# OscillatorShield.net
KiCad netlist of a schematic drawn in EAGLE
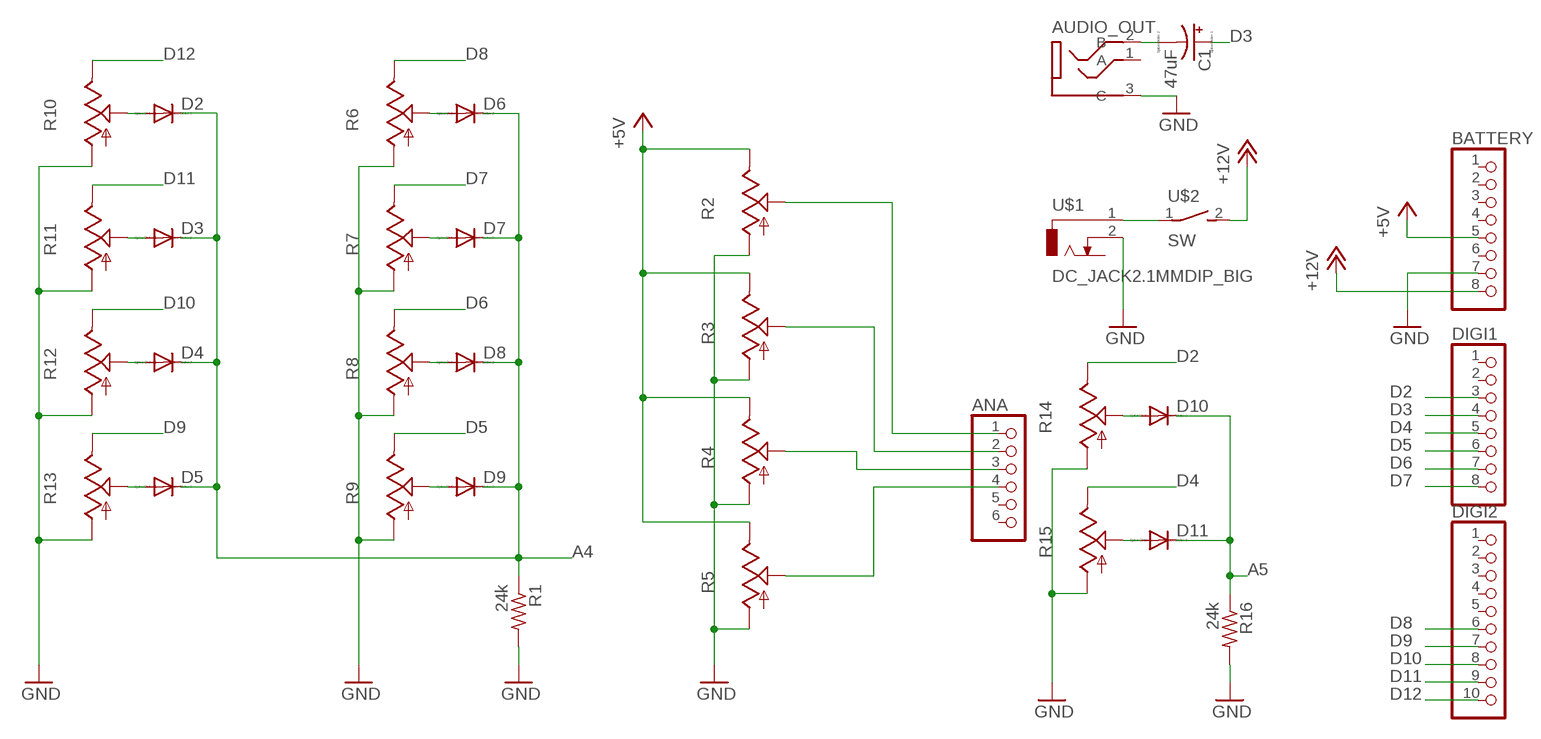
[diagram p0: schematic, sheet 1]

(export (version "E")
  (design (tool "Eeschema 10.0.6"))
  (components
    (comp (ref "ANA")
      (value "PINHD-1X6")
      (footprint "eagle-import:1X06")
      (libsource (lib "eagle-import") (part "PINHD-1X6"))
    )
    (comp (ref "AUDIO_OUT")
      (value "3CON_3.5MMPLUG")
      (footprint "eagle-import:3PIN_DIP")
      (libsource (lib "eagle-import") (part "3CON_3.5MMPLUG"))
    )
    (comp (ref "BATTERY")
      (value "PINHD-1X8")
      (footprint "eagle-import:1X08")
      (libsource (lib "eagle-import") (part "PINHD-1X8"))
    )
    (comp (ref "C1")
      (value "47uF")
      (footprint "eagle-import:E2,5-6")
      (libsource (lib "eagle-import") (part "CPOL-USE2.5-6"))
    )
    (comp (ref "D2")
      (value "DIODE-SOD123")
      (footprint "eagle-import:SOD123")
      (libsource (lib "eagle-import") (part "DIODE-SOD123"))
    )
    (comp (ref "D3")
      (value "DIODE-SOD123")
      (footprint "eagle-import:SOD123")
      (libsource (lib "eagle-import") (part "DIODE-SOD123"))
    )
    (comp (ref "D4")
      (value "DIODE-SOD123")
      (footprint "eagle-import:SOD123")
      (libsource (lib "eagle-import") (part "DIODE-SOD123"))
    )
    (comp (ref "D5")
      (value "DIODE-SOD123")
      (footprint "eagle-import:SOD123")
      (libsource (lib "eagle-import") (part "DIODE-SOD123"))
    )
    (comp (ref "D6")
      (value "DIODE-SOD123")
      (footprint "eagle-import:SOD123")
      (libsource (lib "eagle-import") (part "DIODE-SOD123"))
    )
    (comp (ref "D7")
      (value "DIODE-SOD123")
      (footprint "eagle-import:SOD123")
      (libsource (lib "eagle-import") (part "DIODE-SOD123"))
    )
    (comp (ref "D8")
      (value "DIODE-SOD123")
      (footprint "eagle-import:SOD123")
      (libsource (lib "eagle-import") (part "DIODE-SOD123"))
    )
    (comp (ref "D9")
      (value "DIODE-SOD123")
      (footprint "eagle-import:SOD123")
      (libsource (lib "eagle-import") (part "DIODE-SOD123"))
    )
    (comp (ref "D10")
      (value "DIODE-SOD123")
      (footprint "eagle-import:SOD123")
      (libsource (lib "eagle-import") (part "DIODE-SOD123"))
    )
    (comp (ref "D11")
      (value "DIODE-SOD123")
      (footprint "eagle-import:SOD123")
      (libsource (lib "eagle-import") (part "DIODE-SOD123"))
    )
    (comp (ref "DIGI1")
      (value "PINHD-1X8")
      (footprint "eagle-import:1X08")
      (libsource (lib "eagle-import") (part "PINHD-1X8"))
    )
    (comp (ref "DIGI2")
      (value "PINHD-1X10")
      (footprint "eagle-import:1X10")
      (libsource (lib "eagle-import") (part "PINHD-1X10"))
    )
    (comp (ref "R1")
      (value "24k")
      (footprint "eagle-import:R1206")
      (libsource (lib "eagle-import") (part "R-US_R1206"))
    )
    (comp (ref "R2")
      (value "TRIM_US-RJ9W")
      (footprint "eagle-import:RJ9W")
      (libsource (lib "eagle-import") (part "TRIM_US-RJ9W"))
    )
    (comp (ref "R3")
      (value "TRIM_US-RJ9W")
      (footprint "eagle-import:RJ9W")
      (libsource (lib "eagle-import") (part "TRIM_US-RJ9W"))
    )
    (comp (ref "R4")
      (value "TRIM_US-RJ9W")
      (footprint "eagle-import:RJ9W")
      (libsource (lib "eagle-import") (part "TRIM_US-RJ9W"))
    )
    (comp (ref "R5")
      (value "TRIM_US-RJ9W")
      (footprint "eagle-import:RJ9W")
      (libsource (lib "eagle-import") (part "TRIM_US-RJ9W"))
    )
    (comp (ref "R6")
      (value "TRIM_US-RJ9W")
      (footprint "eagle-import:RJ9W")
      (libsource (lib "eagle-import") (part "TRIM_US-RJ9W"))
    )
    (comp (ref "R7")
      (value "TRIM_US-RJ9W")
      (footprint "eagle-import:RJ9W")
      (libsource (lib "eagle-import") (part "TRIM_US-RJ9W"))
    )
    (comp (ref "R8")
      (value "TRIM_US-RJ9W")
      (footprint "eagle-import:RJ9W")
      (libsource (lib "eagle-import") (part "TRIM_US-RJ9W"))
    )
    (comp (ref "R9")
      (value "TRIM_US-RJ9W")
      (footprint "eagle-import:RJ9W")
      (libsource (lib "eagle-import") (part "TRIM_US-RJ9W"))
    )
    (comp (ref "R10")
      (value "TRIM_US-RJ9W")
      (footprint "eagle-import:RJ9W")
      (libsource (lib "eagle-import") (part "TRIM_US-RJ9W"))
    )
    (comp (ref "R11")
      (value "TRIM_US-RJ9W")
      (footprint "eagle-import:RJ9W")
      (libsource (lib "eagle-import") (part "TRIM_US-RJ9W"))
    )
    (comp (ref "R12")
      (value "TRIM_US-RJ9W")
      (footprint "eagle-import:RJ9W")
      (libsource (lib "eagle-import") (part "TRIM_US-RJ9W"))
    )
    (comp (ref "R13")
      (value "TRIM_US-RJ9W")
      (footprint "eagle-import:RJ9W")
      (libsource (lib "eagle-import") (part "TRIM_US-RJ9W"))
    )
    (comp (ref "R14")
      (value "TRIM_US-RJ9W")
      (footprint "eagle-import:RJ9W")
      (libsource (lib "eagle-import") (part "TRIM_US-RJ9W"))
    )
    (comp (ref "R15")
      (value "TRIM_US-RJ9W")
      (footprint "eagle-import:RJ9W")
      (libsource (lib "eagle-import") (part "TRIM_US-RJ9W"))
    )
    (comp (ref "R16")
      (value "24k")
      (footprint "eagle-import:R1206")
      (libsource (lib "eagle-import") (part "R-US_R1206"))
    )
    (comp (ref "U$1")
      (value "DC_JACK2.1MMDIP_BIG")
      (footprint "eagle-import:2PIN_DIP_BIG")
      (libsource (lib "eagle-import") (part "DC_JACK2.1MMDIP_BIG"))
    )
    (comp (ref "U$2")
      (value "SW")
      (footprint "eagle-import:2PIN_DIP_BIG")
      (libsource (lib "eagle-import") (part "SW"))
    )
  )
  (nets
    (net (code "1") (name "+5V") (class "Default")
      (node (ref "BATTERY") (pin "5") (pinfunction "5_5") (pintype "passive"))
      (node (ref "R2") (pin "E") (pinfunction "E_E") (pintype "passive"))
      (node (ref "R3") (pin "E") (pinfunction "E_E") (pintype "passive"))
      (node (ref "R4") (pin "E") (pinfunction "E_E") (pintype "passive"))
      (node (ref "R5") (pin "E") (pinfunction "E_E") (pintype "passive"))
    )
    (net (code "2") (name "+12V") (class "Default")
      (node (ref "BATTERY") (pin "8") (pinfunction "8_8") (pintype "passive"))
      (node (ref "U$2") (pin "2") (pinfunction "S_2") (pintype "passive"))
    )
    (net (code "3") (name "/A4") (class "Default")
      (node (ref "D2") (pin "C") (pinfunction "C_C") (pintype "passive"))
      (node (ref "D3") (pin "C") (pinfunction "C_C") (pintype "passive"))
      (node (ref "D4") (pin "C") (pinfunction "C_C") (pintype "passive"))
      (node (ref "D5") (pin "C") (pinfunction "C_C") (pintype "passive"))
      (node (ref "D6") (pin "C") (pinfunction "C_C") (pintype "passive"))
      (node (ref "D7") (pin "C") (pinfunction "C_C") (pintype "passive"))
      (node (ref "D8") (pin "C") (pinfunction "C_C") (pintype "passive"))
      (node (ref "D9") (pin "C") (pinfunction "C_C") (pintype "passive"))
      (node (ref "R1") (pin "1") (pinfunction "1_1") (pintype "passive"))
    )
    (net (code "4") (name "/A5") (class "Default")
      (node (ref "D10") (pin "C") (pinfunction "C_C") (pintype "passive"))
      (node (ref "D11") (pin "C") (pinfunction "C_C") (pintype "passive"))
      (node (ref "R16") (pin "1") (pinfunction "1_1") (pintype "passive"))
    )
    (net (code "5") (name "/D2") (class "Default")
      (node (ref "DIGI1") (pin "3") (pinfunction "3_3") (pintype "passive"))
      (node (ref "R14") (pin "E") (pinfunction "E_E") (pintype "passive"))
    )
    (net (code "6") (name "/D3") (class "Default")
      (node (ref "C1") (pin "+") (pinfunction "+_+") (pintype "passive"))
      (node (ref "DIGI1") (pin "4") (pinfunction "4_4") (pintype "passive"))
    )
    (net (code "7") (name "/D4") (class "Default")
      (node (ref "DIGI1") (pin "5") (pinfunction "5_5") (pintype "passive"))
      (node (ref "R15") (pin "E") (pinfunction "E_E") (pintype "passive"))
    )
    (net (code "8") (name "/D5") (class "Default")
      (node (ref "DIGI1") (pin "6") (pinfunction "6_6") (pintype "passive"))
      (node (ref "R9") (pin "E") (pinfunction "E_E") (pintype "passive"))
    )
    (net (code "9") (name "/D6") (class "Default")
      (node (ref "DIGI1") (pin "7") (pinfunction "7_7") (pintype "passive"))
      (node (ref "R8") (pin "E") (pinfunction "E_E") (pintype "passive"))
    )
    (net (code "10") (name "/D7") (class "Default")
      (node (ref "DIGI1") (pin "8") (pinfunction "8_8") (pintype "passive"))
      (node (ref "R7") (pin "E") (pinfunction "E_E") (pintype "passive"))
    )
    (net (code "11") (name "/D8") (class "Default")
      (node (ref "DIGI2") (pin "6") (pinfunction "6_6") (pintype "passive"))
      (node (ref "R6") (pin "E") (pinfunction "E_E") (pintype "passive"))
    )
    (net (code "12") (name "/D9") (class "Default")
      (node (ref "DIGI2") (pin "7") (pinfunction "7_7") (pintype "passive"))
      (node (ref "R13") (pin "E") (pinfunction "E_E") (pintype "passive"))
    )
    (net (code "13") (name "/D10") (class "Default")
      (node (ref "DIGI2") (pin "8") (pinfunction "8_8") (pintype "passive"))
      (node (ref "R12") (pin "E") (pinfunction "E_E") (pintype "passive"))
    )
    (net (code "14") (name "/D11") (class "Default")
      (node (ref "DIGI2") (pin "9") (pinfunction "9_9") (pintype "passive"))
      (node (ref "R11") (pin "E") (pinfunction "E_E") (pintype "passive"))
    )
    (net (code "15") (name "/D12") (class "Default")
      (node (ref "DIGI2") (pin "10") (pinfunction "10_10") (pintype "passive"))
      (node (ref "R10") (pin "E") (pinfunction "E_E") (pintype "passive"))
    )
    (net (code "16") (name "GND") (class "Default")
      (node (ref "AUDIO_OUT") (pin "3") (pinfunction "C_3") (pintype "bidirectional"))
      (node (ref "BATTERY") (pin "7") (pinfunction "7_7") (pintype "passive"))
      (node (ref "R1") (pin "2") (pinfunction "2_2") (pintype "passive"))
      (node (ref "R10") (pin "A") (pinfunction "A_A") (pintype "passive"))
      (node (ref "R11") (pin "A") (pinfunction "A_A") (pintype "passive"))
      (node (ref "R12") (pin "A") (pinfunction "A_A") (pintype "passive"))
      (node (ref "R13") (pin "A") (pinfunction "A_A") (pintype "passive"))
      (node (ref "R14") (pin "A") (pinfunction "A_A") (pintype "passive"))
      (node (ref "R15") (pin "A") (pinfunction "A_A") (pintype "passive"))
      (node (ref "R16") (pin "2") (pinfunction "2_2") (pintype "passive"))
      (node (ref "R2") (pin "A") (pinfunction "A_A") (pintype "passive"))
      (node (ref "R3") (pin "A") (pinfunction "A_A") (pintype "passive"))
      (node (ref "R4") (pin "A") (pinfunction "A_A") (pintype "passive"))
      (node (ref "R5") (pin "A") (pinfunction "A_A") (pintype "passive"))
      (node (ref "R6") (pin "A") (pinfunction "A_A") (pintype "passive"))
      (node (ref "R7") (pin "A") (pinfunction "A_A") (pintype "passive"))
      (node (ref "R8") (pin "A") (pinfunction "A_A") (pintype "passive"))
      (node (ref "R9") (pin "A") (pinfunction "A_A") (pintype "passive"))
      (node (ref "U$1") (pin "2") (pinfunction "2_2") (pintype "passive"))
    )
    (net (code "17") (name "Net-(ANA-Pad1)") (class "Default")
      (node (ref "ANA") (pin "1") (pinfunction "1_1") (pintype "passive"))
      (node (ref "R2") (pin "S") (pinfunction "S_S") (pintype "passive"))
    )
    (net (code "18") (name "Net-(ANA-Pad2)") (class "Default")
      (node (ref "ANA") (pin "2") (pinfunction "2_2") (pintype "passive"))
      (node (ref "R3") (pin "S") (pinfunction "S_S") (pintype "passive"))
    )
    (net (code "19") (name "Net-(ANA-Pad3)") (class "Default")
      (node (ref "ANA") (pin "3") (pinfunction "3_3") (pintype "passive"))
      (node (ref "R4") (pin "S") (pinfunction "S_S") (pintype "passive"))
    )
    (net (code "20") (name "Net-(ANA-Pad4)") (class "Default")
      (node (ref "ANA") (pin "4") (pinfunction "4_4") (pintype "passive"))
      (node (ref "R5") (pin "S") (pinfunction "S_S") (pintype "passive"))
    )
    (net (code "21") (name "Net-(AUDIO_OUT-B)") (class "Default")
      (node (ref "AUDIO_OUT") (pin "2") (pinfunction "B_2") (pintype "bidirectional"))
      (node (ref "C1") (pin "-") (pinfunction "-_-") (pintype "passive"))
    )
    (net (code "22") (name "Net-(D2-PadA)") (class "Default")
      (node (ref "D2") (pin "A") (pinfunction "A_A") (pintype "passive"))
      (node (ref "R10") (pin "S") (pinfunction "S_S") (pintype "passive"))
    )
    (net (code "23") (name "Net-(D3-PadA)") (class "Default")
      (node (ref "D3") (pin "A") (pinfunction "A_A") (pintype "passive"))
      (node (ref "R11") (pin "S") (pinfunction "S_S") (pintype "passive"))
    )
    (net (code "24") (name "Net-(D4-PadA)") (class "Default")
      (node (ref "D4") (pin "A") (pinfunction "A_A") (pintype "passive"))
      (node (ref "R12") (pin "S") (pinfunction "S_S") (pintype "passive"))
    )
    (net (code "25") (name "Net-(D5-PadA)") (class "Default")
      (node (ref "D5") (pin "A") (pinfunction "A_A") (pintype "passive"))
      (node (ref "R13") (pin "S") (pinfunction "S_S") (pintype "passive"))
    )
    (net (code "26") (name "Net-(D6-PadA)") (class "Default")
      (node (ref "D6") (pin "A") (pinfunction "A_A") (pintype "passive"))
      (node (ref "R6") (pin "S") (pinfunction "S_S") (pintype "passive"))
    )
    (net (code "27") (name "Net-(D7-PadA)") (class "Default")
      (node (ref "D7") (pin "A") (pinfunction "A_A") (pintype "passive"))
      (node (ref "R7") (pin "S") (pinfunction "S_S") (pintype "passive"))
    )
    (net (code "28") (name "Net-(D8-PadA)") (class "Default")
      (node (ref "D8") (pin "A") (pinfunction "A_A") (pintype "passive"))
      (node (ref "R8") (pin "S") (pinfunction "S_S") (pintype "passive"))
    )
    (net (code "29") (name "Net-(D9-PadA)") (class "Default")
      (node (ref "D9") (pin "A") (pinfunction "A_A") (pintype "passive"))
      (node (ref "R9") (pin "S") (pinfunction "S_S") (pintype "passive"))
    )
    (net (code "30") (name "Net-(D10-PadA)") (class "Default")
      (node (ref "D10") (pin "A") (pinfunction "A_A") (pintype "passive"))
      (node (ref "R14") (pin "S") (pinfunction "S_S") (pintype "passive"))
    )
    (net (code "31") (name "Net-(D11-PadA)") (class "Default")
      (node (ref "D11") (pin "A") (pinfunction "A_A") (pintype "passive"))
      (node (ref "R15") (pin "S") (pinfunction "S_S") (pintype "passive"))
    )
    (net (code "32") (name "Net-(U$2-P)") (class "Default")
      (node (ref "U$1") (pin "1") (pinfunction "1_1") (pintype "passive"))
      (node (ref "U$2") (pin "1") (pinfunction "P_1") (pintype "passive"))
    )
    (net (code "33") (name "unconnected-(ANA-Pad5)") (class "Default")
      (node (ref "ANA") (pin "5") (pinfunction "5_5") (pintype "passive"))
    )
    (net (code "34") (name "unconnected-(ANA-Pad6)") (class "Default")
      (node (ref "ANA") (pin "6") (pinfunction "6_6") (pintype "passive"))
    )
    (net (code "35") (name "unconnected-(AUDIO_OUT-A-Pad1)") (class "Default")
      (node (ref "AUDIO_OUT") (pin "1") (pinfunction "A_1") (pintype "bidirectional"))
    )
    (net (code "36") (name "unconnected-(BATTERY-Pad1)") (class "Default")
      (node (ref "BATTERY") (pin "1") (pinfunction "1_1") (pintype "passive"))
    )
    (net (code "37") (name "unconnected-(BATTERY-Pad2)") (class "Default")
      (node (ref "BATTERY") (pin "2") (pinfunction "2_2") (pintype "passive"))
    )
    (net (code "38") (name "unconnected-(BATTERY-Pad3)") (class "Default")
      (node (ref "BATTERY") (pin "3") (pinfunction "3_3") (pintype "passive"))
    )
    (net (code "39") (name "unconnected-(BATTERY-Pad4)") (class "Default")
      (node (ref "BATTERY") (pin "4") (pinfunction "4_4") (pintype "passive"))
    )
    (net (code "40") (name "unconnected-(BATTERY-Pad6)") (class "Default")
      (node (ref "BATTERY") (pin "6") (pinfunction "6_6") (pintype "passive"))
    )
    (net (code "41") (name "unconnected-(DIGI1-Pad1)") (class "Default")
      (node (ref "DIGI1") (pin "1") (pinfunction "1_1") (pintype "passive"))
    )
    (net (code "42") (name "unconnected-(DIGI1-Pad2)") (class "Default")
      (node (ref "DIGI1") (pin "2") (pinfunction "2_2") (pintype "passive"))
    )
    (net (code "43") (name "unconnected-(DIGI2-Pad1)") (class "Default")
      (node (ref "DIGI2") (pin "1") (pinfunction "1_1") (pintype "passive"))
    )
    (net (code "44") (name "unconnected-(DIGI2-Pad2)") (class "Default")
      (node (ref "DIGI2") (pin "2") (pinfunction "2_2") (pintype "passive"))
    )
    (net (code "45") (name "unconnected-(DIGI2-Pad3)") (class "Default")
      (node (ref "DIGI2") (pin "3") (pinfunction "3_3") (pintype "passive"))
    )
    (net (code "46") (name "unconnected-(DIGI2-Pad4)") (class "Default")
      (node (ref "DIGI2") (pin "4") (pinfunction "4_4") (pintype "passive"))
    )
    (net (code "47") (name "unconnected-(DIGI2-Pad5)") (class "Default")
      (node (ref "DIGI2") (pin "5") (pinfunction "5_5") (pintype "passive"))
    )
  )
)
